# MCU.net
KiCad netlist of a schematic drawn in Altium Designer
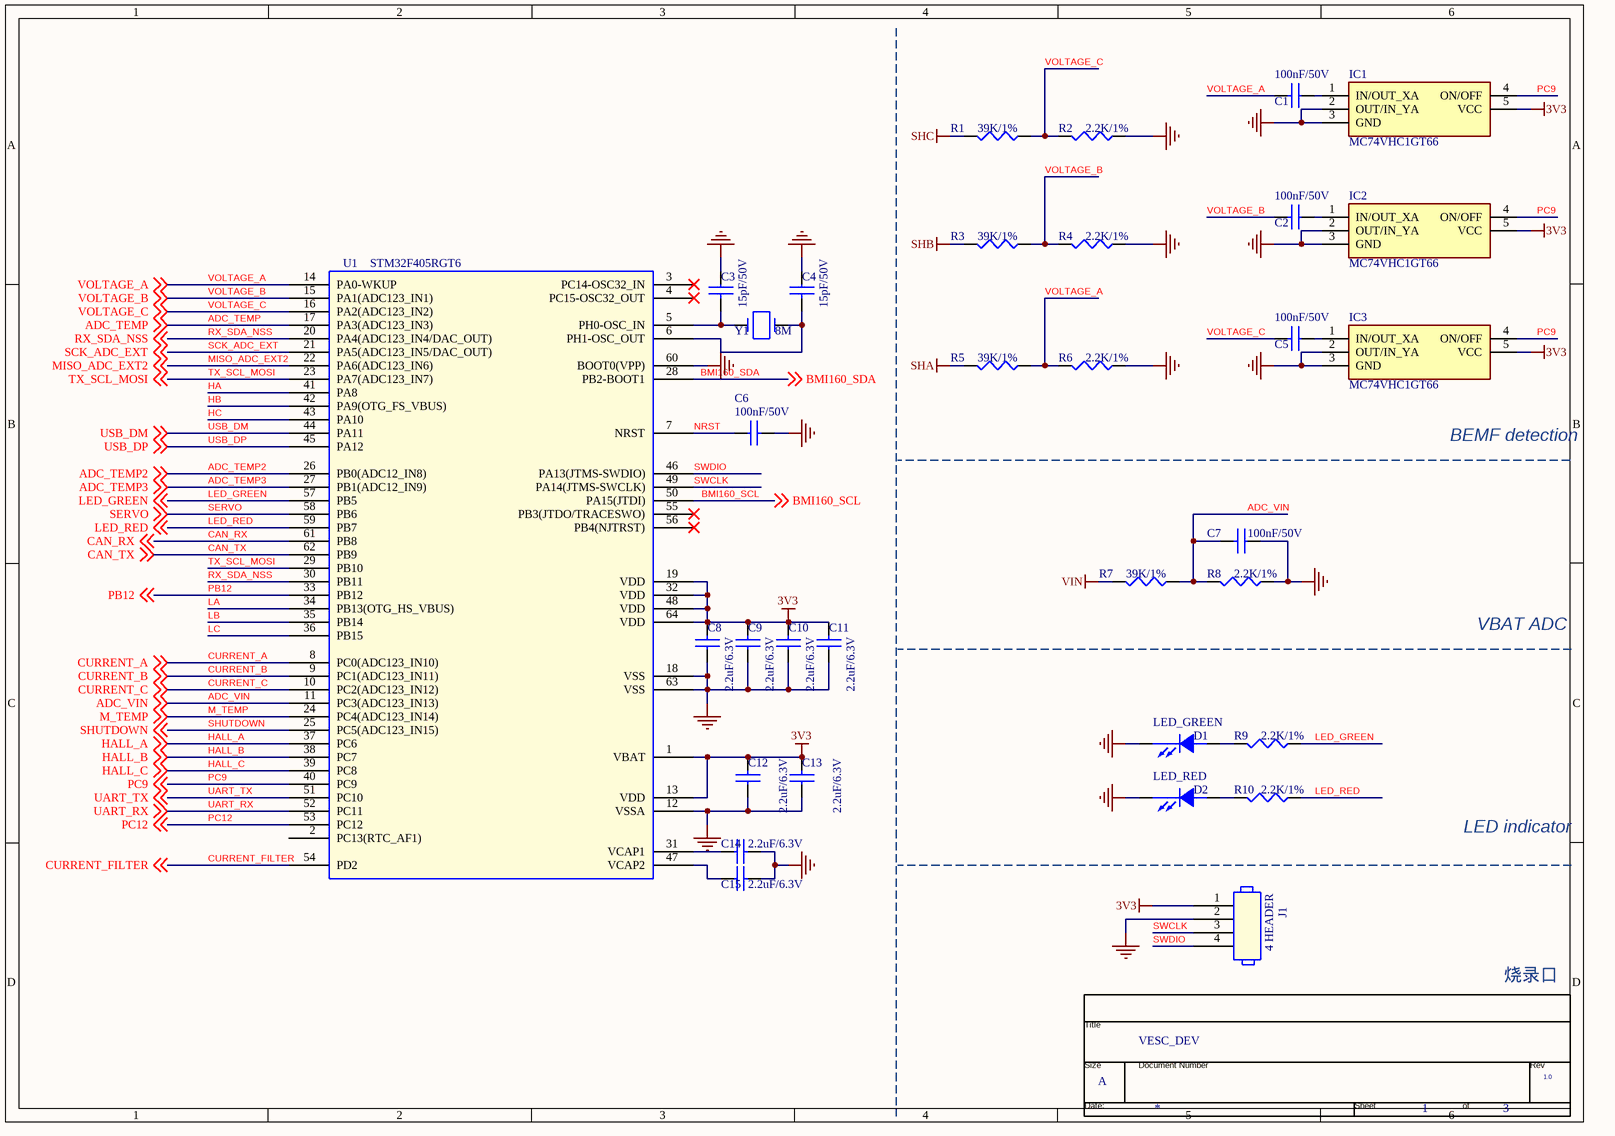
[diagram p0: MCU.SchDoc]

(export (version "E")
  (design (tool "Eeschema 10.0.6"))
  (components
    (comp (ref "C1") (value "100nF/50V") (footprint "C0402") (libsource (lib "*") (part "CAP NP")))
    (comp (ref "C2") (value "100nF/50V") (footprint "C0402") (libsource (lib "*") (part "CAP NP")))
    (comp (ref "C3") (value "15pF/50V") (footprint "C0402") (libsource (lib "*") (part "CAP NP")))
    (comp (ref "C4") (value "15pF/50V") (footprint "C0402") (libsource (lib "*") (part "CAP NP")))
    (comp (ref "C5") (value "100nF/50V") (footprint "C0402") (libsource (lib "*") (part "CAP NP")))
    (comp (ref "C6") (value "100nF/50V") (footprint "C0402") (libsource (lib "*") (part "CAP NP")))
    (comp (ref "C7") (value "100nF/50V") (footprint "C0402") (libsource (lib "*") (part "CAP NP")))
    (comp (ref "C8") (value "2.2uF/6.3V") (footprint "C0402") (libsource (lib "*") (part "CAP NP")))
    (comp (ref "C9") (value "2.2uF/6.3V") (footprint "C0402") (libsource (lib "*") (part "CAP NP")))
    (comp (ref "C10") (value "2.2uF/6.3V") (footprint "C0402") (libsource (lib "*") (part "CAP NP")))
    (comp (ref "C11") (value "2.2uF/6.3V") (footprint "C0402") (libsource (lib "*") (part "CAP NP")))
    (comp (ref "C12") (value "2.2uF/6.3V") (footprint "C0402") (libsource (lib "*") (part "CAP NP")))
    (comp (ref "C13") (value "2.2uF/6.3V") (footprint "C0402") (libsource (lib "*") (part "CAP NP")))
    (comp (ref "C14") (value "2.2uF/6.3V") (footprint "C0402") (libsource (lib "*") (part "CAP NP")))
    (comp (ref "C15") (value "2.2uF/6.3V") (footprint "C0402") (libsource (lib "*") (part "CAP NP")))
    (comp (ref "D1") (value "LED_GREEN") (footprint "LED0603") (libsource (lib "*") (part "LED")))
    (comp (ref "D2") (value "LED_RED") (footprint "LED0603") (libsource (lib "*") (part "LED")))
    (comp (ref "IC1")
      (value "MC74VHC1GT66")
      (footprint "SamacSys:SOT95P275X110-5N")
      (description "Integrated Circuit")
      (libsource (lib "VESC_DEVICE_Library") (part "MC74VHC1GT66"))
    )
    (comp (ref "IC2")
      (value "MC74VHC1GT66")
      (footprint "SamacSys:SOT95P275X110-5N")
      (description "Integrated Circuit")
      (libsource (lib "VESC_DEVICE_Library") (part "MC74VHC1GT66"))
    )
    (comp (ref "IC3")
      (value "MC74VHC1GT66")
      (footprint "SamacSys:SOT95P275X110-5N")
      (description "Integrated Circuit")
      (libsource (lib "VESC_DEVICE_Library") (part "MC74VHC1GT66"))
    )
    (comp (ref "J1") (value "4 HEADER") (footprint "ISP-4P-2_54") (libsource (lib "*") (part "4 HEADER")))
    (comp (ref "R1") (value "39K/1%") (footprint "R0402") (libsource (lib "*") (part "RESISTOR")))
    (comp (ref "R2") (value "2.2K/1%") (footprint "R0402") (libsource (lib "*") (part "RESISTOR")))
    (comp (ref "R3") (value "39K/1%") (footprint "R0402") (libsource (lib "*") (part "RESISTOR")))
    (comp (ref "R4") (value "2.2K/1%") (footprint "R0402") (libsource (lib "*") (part "RESISTOR")))
    (comp (ref "R5") (value "39K/1%") (footprint "R0402") (libsource (lib "*") (part "RESISTOR")))
    (comp (ref "R6") (value "2.2K/1%") (footprint "R0402") (libsource (lib "*") (part "RESISTOR")))
    (comp (ref "R7") (value "39K/1%") (footprint "R0402") (libsource (lib "*") (part "RESISTOR")))
    (comp (ref "R8") (value "2.2K/1%") (footprint "R0402") (libsource (lib "*") (part "RESISTOR")))
    (comp (ref "R9") (value "2.2K/1%") (footprint "R0402") (libsource (lib "*") (part "RESISTOR")))
    (comp (ref "R10") (value "2.2K/1%") (footprint "R0402") (libsource (lib "*") (part "RESISTOR")))
    (comp (ref "U1")
      (value "STM32F405RGT6")
      (footprint "LQFP64_10X10_05P")
      (libsource (lib "*") (part "STM32F405RGT6"))
    )
    (comp (ref "Y1") (value "8M") (footprint "SMD5032-2P") (libsource (lib "*") (part "CRYSTAL")))
  )
  (nets
    (net (code "1") (name "/HA") (class "Default")
      (node (ref "U1") (pin "41") (pinfunction "PA8_41") (pintype "passive"))
    )
    (net (code "2") (name "/HB") (class "Default")
      (node (ref "U1") (pin "42") (pinfunction "PA9(OTG_FS_VBUS)_42") (pintype "passive"))
    )
    (net (code "3") (name "/HC") (class "Default")
      (node (ref "U1") (pin "43") (pinfunction "PA10_43") (pintype "passive"))
    )
    (net (code "4") (name "/LA") (class "Default")
      (node (ref "U1") (pin "34") (pinfunction "PB13(OTG_HS_VBUS)_34") (pintype "passive"))
    )
    (net (code "5") (name "/LB") (class "Default")
      (node (ref "U1") (pin "35") (pinfunction "PB14_35") (pintype "passive"))
    )
    (net (code "6") (name "/LC") (class "Default")
      (node (ref "U1") (pin "36") (pinfunction "PB15_36") (pintype "passive"))
    )
    (net (code "7") (name "/NRST") (class "Default")
      (node (ref "C6") (pin "1") (pinfunction "1_1") (pintype "passive"))
      (node (ref "U1") (pin "7") (pinfunction "NRST_7") (pintype "passive"))
    )
    (net (code "8") (name "/SWCLK") (class "Default")
      (node (ref "J1") (pin "3") (pinfunction "3_3") (pintype "passive"))
      (node (ref "U1") (pin "49") (pinfunction "PA14(JTMS-SWCLK)_49") (pintype "passive"))
    )
    (net (code "9") (name "/SWDIO") (class "Default")
      (node (ref "J1") (pin "4") (pinfunction "4_4") (pintype "passive"))
      (node (ref "U1") (pin "46") (pinfunction "PA13(JTMS-SWDIO)_46") (pintype "passive"))
    )
    (net (code "10") (name "3V3") (class "Default")
      (node (ref "C10") (pin "2") (pinfunction "2_2") (pintype "passive"))
      (node (ref "C11") (pin "2") (pinfunction "2_2") (pintype "passive"))
      (node (ref "C12") (pin "2") (pinfunction "2_2") (pintype "passive"))
      (node (ref "C13") (pin "2") (pinfunction "2_2") (pintype "passive"))
      (node (ref "C8") (pin "2") (pinfunction "2_2") (pintype "passive"))
      (node (ref "C9") (pin "2") (pinfunction "2_2") (pintype "passive"))
      (node (ref "IC1") (pin "5") (pinfunction "VCC_5") (pintype "passive"))
      (node (ref "IC2") (pin "5") (pinfunction "VCC_5") (pintype "passive"))
      (node (ref "IC3") (pin "5") (pinfunction "VCC_5") (pintype "passive"))
      (node (ref "J1") (pin "1") (pinfunction "1_1") (pintype "passive"))
      (node (ref "U1") (pin "1") (pinfunction "VBAT_1") (pintype "power_in"))
      (node (ref "U1") (pin "13") (pinfunction "VDD_13") (pintype "power_in"))
      (node (ref "U1") (pin "19") (pinfunction "VDD_19") (pintype "power_in"))
      (node (ref "U1") (pin "32") (pinfunction "VDD_32") (pintype "power_in"))
      (node (ref "U1") (pin "48") (pinfunction "VDD_48") (pintype "power_in"))
      (node (ref "U1") (pin "64") (pinfunction "VDD_64") (pintype "power_in"))
    )
    (net (code "11") (name "ADC_TEMP") (class "Default")
      (node (ref "U1") (pin "17") (pinfunction "PA3(ADC123_IN3)_17") (pintype "passive"))
    )
    (net (code "12") (name "ADC_TEMP2") (class "Default")
      (node (ref "U1") (pin "26") (pinfunction "PB0(ADC12_IN8)_26") (pintype "passive"))
    )
    (net (code "13") (name "ADC_TEMP3") (class "Default")
      (node (ref "U1") (pin "27") (pinfunction "PB1(ADC12_IN9)_27") (pintype "passive"))
    )
    (net (code "14") (name "ADC_VIN") (class "Default")
      (node (ref "C7") (pin "2") (pinfunction "2_2") (pintype "passive"))
      (node (ref "R7") (pin "1") (pinfunction "1_1") (pintype "passive"))
      (node (ref "R8") (pin "2") (pinfunction "2_2") (pintype "passive"))
      (node (ref "U1") (pin "11") (pinfunction "PC3(ADC123_IN13)_11") (pintype "passive"))
    )
    (net (code "15") (name "BMI160_SCL") (class "Default")
      (node (ref "U1") (pin "50") (pinfunction "PA15(JTDI)_50") (pintype "passive"))
    )
    (net (code "16") (name "BMI160_SDA") (class "Default")
      (node (ref "U1") (pin "28") (pinfunction "PB2-BOOT1_28") (pintype "passive"))
    )
    (net (code "17") (name "CAN_RX") (class "Default")
      (node (ref "U1") (pin "61") (pinfunction "PB8_61") (pintype "passive"))
    )
    (net (code "18") (name "CAN_TX") (class "Default")
      (node (ref "U1") (pin "62") (pinfunction "PB9_62") (pintype "passive"))
    )
    (net (code "19") (name "CURRENT_A") (class "Default")
      (node (ref "U1") (pin "8") (pinfunction "PC0(ADC123_IN10)_8") (pintype "passive"))
    )
    (net (code "20") (name "CURRENT_B") (class "Default")
      (node (ref "U1") (pin "9") (pinfunction "PC1(ADC123_IN11)_9") (pintype "passive"))
    )
    (net (code "21") (name "CURRENT_C") (class "Default")
      (node (ref "U1") (pin "10") (pinfunction "PC2(ADC123_IN12)_10") (pintype "passive"))
    )
    (net (code "22") (name "CURRENT_FILTER") (class "Default")
      (node (ref "U1") (pin "54") (pinfunction "PD2_54") (pintype "passive"))
    )
    (net (code "23") (name "GND") (class "Default")
      (node (ref "C10") (pin "1") (pinfunction "1_1") (pintype "passive"))
      (node (ref "C11") (pin "1") (pinfunction "1_1") (pintype "passive"))
      (node (ref "C12") (pin "1") (pinfunction "1_1") (pintype "passive"))
      (node (ref "C13") (pin "1") (pinfunction "1_1") (pintype "passive"))
      (node (ref "C14") (pin "2") (pinfunction "2_2") (pintype "passive"))
      (node (ref "C15") (pin "2") (pinfunction "2_2") (pintype "passive"))
      (node (ref "C3") (pin "1") (pinfunction "1_1") (pintype "passive"))
      (node (ref "C4") (pin "1") (pinfunction "1_1") (pintype "passive"))
      (node (ref "C6") (pin "2") (pinfunction "2_2") (pintype "passive"))
      (node (ref "C7") (pin "1") (pinfunction "1_1") (pintype "passive"))
      (node (ref "C8") (pin "1") (pinfunction "1_1") (pintype "passive"))
      (node (ref "C9") (pin "1") (pinfunction "1_1") (pintype "passive"))
      (node (ref "D1") (pin "1") (pinfunction "CATHODE_1") (pintype "passive"))
      (node (ref "D2") (pin "1") (pinfunction "CATHODE_1") (pintype "passive"))
      (node (ref "IC1") (pin "2") (pinfunction "OUT/IN_YA_2") (pintype "passive"))
      (node (ref "IC1") (pin "3") (pinfunction "GND_3") (pintype "passive"))
      (node (ref "IC2") (pin "2") (pinfunction "OUT/IN_YA_2") (pintype "passive"))
      (node (ref "IC2") (pin "3") (pinfunction "GND_3") (pintype "passive"))
      (node (ref "IC3") (pin "2") (pinfunction "OUT/IN_YA_2") (pintype "passive"))
      (node (ref "IC3") (pin "3") (pinfunction "GND_3") (pintype "passive"))
      (node (ref "J1") (pin "2") (pinfunction "2_2") (pintype "passive"))
      (node (ref "R2") (pin "1") (pinfunction "1_1") (pintype "passive"))
      (node (ref "R4") (pin "1") (pinfunction "1_1") (pintype "passive"))
      (node (ref "R6") (pin "1") (pinfunction "1_1") (pintype "passive"))
      (node (ref "R8") (pin "1") (pinfunction "1_1") (pintype "passive"))
      (node (ref "U1") (pin "12") (pinfunction "VSSA_12") (pintype "power_in"))
      (node (ref "U1") (pin "18") (pinfunction "VSS_18") (pintype "power_in"))
      (node (ref "U1") (pin "60") (pinfunction "BOOT0(VPP)_60") (pintype "passive"))
      (node (ref "U1") (pin "63") (pinfunction "VSS_63") (pintype "power_in"))
    )
    (net (code "24") (name "HALL_A") (class "Default")
      (node (ref "U1") (pin "37") (pinfunction "PC6_37") (pintype "passive"))
    )
    (net (code "25") (name "HALL_B") (class "Default")
      (node (ref "U1") (pin "38") (pinfunction "PC7_38") (pintype "passive"))
    )
    (net (code "26") (name "HALL_C") (class "Default")
      (node (ref "U1") (pin "39") (pinfunction "PC8_39") (pintype "passive"))
    )
    (net (code "27") (name "LED_GREEN") (class "Default")
      (node (ref "R9") (pin "1") (pinfunction "1_1") (pintype "passive"))
      (node (ref "U1") (pin "57") (pinfunction "PB5_57") (pintype "passive"))
    )
    (net (code "28") (name "LED_RED") (class "Default")
      (node (ref "R10") (pin "1") (pinfunction "1_1") (pintype "passive"))
      (node (ref "U1") (pin "59") (pinfunction "PB7_59") (pintype "passive"))
    )
    (net (code "29") (name "MISO_ADC_EXT2") (class "Default")
      (node (ref "U1") (pin "22") (pinfunction "PA6(ADC123_IN6)_22") (pintype "passive"))
    )
    (net (code "30") (name "M_TEMP") (class "Default")
      (node (ref "U1") (pin "24") (pinfunction "PC4(ADC123_IN14)_24") (pintype "passive"))
    )
    (net (code "31") (name "Net-(D1-ANODE)") (class "Default")
      (node (ref "D1") (pin "2") (pinfunction "ANODE_2") (pintype "passive"))
      (node (ref "R9") (pin "2") (pinfunction "2_2") (pintype "passive"))
    )
    (net (code "32") (name "Net-(D2-ANODE)") (class "Default")
      (node (ref "D2") (pin "2") (pinfunction "ANODE_2") (pintype "passive"))
      (node (ref "R10") (pin "2") (pinfunction "2_2") (pintype "passive"))
    )
    (net (code "33") (name "Net-(IC1-IN{slash}OUT_XA)") (class "Default")
      (node (ref "C1") (pin "1") (pinfunction "1_1") (pintype "passive"))
      (node (ref "IC1") (pin "1") (pinfunction "IN/OUT_XA_1") (pintype "passive"))
    )
    (net (code "34") (name "Net-(IC2-IN{slash}OUT_XA)") (class "Default")
      (node (ref "C2") (pin "1") (pinfunction "1_1") (pintype "passive"))
      (node (ref "IC2") (pin "1") (pinfunction "IN/OUT_XA_1") (pintype "passive"))
    )
    (net (code "35") (name "Net-(IC3-IN{slash}OUT_XA)") (class "Default")
      (node (ref "C5") (pin "1") (pinfunction "1_1") (pintype "passive"))
      (node (ref "IC3") (pin "1") (pinfunction "IN/OUT_XA_1") (pintype "passive"))
    )
    (net (code "36") (name "Net-(U1-PH0-OSC_IN)") (class "Default")
      (node (ref "C3") (pin "2") (pinfunction "2_2") (pintype "passive"))
      (node (ref "U1") (pin "5") (pinfunction "PH0-OSC_IN_5") (pintype "passive"))
      (node (ref "Y1") (pin "2") (pinfunction "2_2") (pintype "passive"))
    )
    (net (code "37") (name "Net-(U1-PH1-OSC_OUT)") (class "Default")
      (node (ref "C4") (pin "2") (pinfunction "2_2") (pintype "passive"))
      (node (ref "U1") (pin "6") (pinfunction "PH1-OSC_OUT_6") (pintype "passive"))
      (node (ref "Y1") (pin "1") (pinfunction "1_1") (pintype "passive"))
    )
    (net (code "38") (name "Net-(U1-VCAP1)") (class "Default")
      (node (ref "C14") (pin "1") (pinfunction "1_1") (pintype "passive"))
      (node (ref "U1") (pin "31") (pinfunction "VCAP1_31") (pintype "passive"))
    )
    (net (code "39") (name "Net-(U1-VCAP2)") (class "Default")
      (node (ref "C15") (pin "1") (pinfunction "1_1") (pintype "passive"))
      (node (ref "U1") (pin "47") (pinfunction "VCAP2_47") (pintype "passive"))
    )
    (net (code "40") (name "PB12") (class "Default")
      (node (ref "U1") (pin "33") (pinfunction "PB12_33") (pintype "passive"))
    )
    (net (code "41") (name "PC9") (class "Default")
      (node (ref "IC1") (pin "4") (pinfunction "ON/OFF_4") (pintype "passive"))
      (node (ref "IC2") (pin "4") (pinfunction "ON/OFF_4") (pintype "passive"))
      (node (ref "IC3") (pin "4") (pinfunction "ON/OFF_4") (pintype "passive"))
      (node (ref "U1") (pin "40") (pinfunction "PC9_40") (pintype "passive"))
    )
    (net (code "42") (name "PC12") (class "Default")
      (node (ref "U1") (pin "53") (pinfunction "PC12_53") (pintype "passive"))
    )
    (net (code "43") (name "RX_SDA_NSS") (class "Default")
      (node (ref "U1") (pin "20") (pinfunction "PA4(ADC123_IN4/DAC_OUT)_20") (pintype "passive"))
      (node (ref "U1") (pin "30") (pinfunction "PB11_30") (pintype "passive"))
    )
    (net (code "44") (name "SCK_ADC_EXT") (class "Default")
      (node (ref "U1") (pin "21") (pinfunction "PA5(ADC123_IN5/DAC_OUT)_21") (pintype "passive"))
    )
    (net (code "45") (name "SERVO") (class "Default")
      (node (ref "U1") (pin "58") (pinfunction "PB6_58") (pintype "passive"))
    )
    (net (code "46") (name "SHA") (class "Default")
      (node (ref "R5") (pin "2") (pinfunction "2_2") (pintype "passive"))
    )
    (net (code "47") (name "SHB") (class "Default")
      (node (ref "R3") (pin "2") (pinfunction "2_2") (pintype "passive"))
    )
    (net (code "48") (name "SHC") (class "Default")
      (node (ref "R1") (pin "2") (pinfunction "2_2") (pintype "passive"))
    )
    (net (code "49") (name "SHUTDOWN") (class "Default")
      (node (ref "U1") (pin "25") (pinfunction "PC5(ADC123_IN15)_25") (pintype "passive"))
    )
    (net (code "50") (name "TX_SCL_MOSI") (class "Default")
      (node (ref "U1") (pin "23") (pinfunction "PA7(ADC123_IN7)_23") (pintype "passive"))
      (node (ref "U1") (pin "29") (pinfunction "PB10_29") (pintype "passive"))
    )
    (net (code "51") (name "UART_RX") (class "Default")
      (node (ref "U1") (pin "52") (pinfunction "PC11_52") (pintype "passive"))
    )
    (net (code "52") (name "UART_TX") (class "Default")
      (node (ref "U1") (pin "51") (pinfunction "PC10_51") (pintype "passive"))
    )
    (net (code "53") (name "USB_DM") (class "Default")
      (node (ref "U1") (pin "44") (pinfunction "PA11_44") (pintype "passive"))
    )
    (net (code "54") (name "USB_DP") (class "Default")
      (node (ref "U1") (pin "45") (pinfunction "PA12_45") (pintype "passive"))
    )
    (net (code "55") (name "VIN") (class "Default")
      (node (ref "R7") (pin "2") (pinfunction "2_2") (pintype "passive"))
    )
    (net (code "56") (name "VOLTAGE_A") (class "Default")
      (node (ref "C1") (pin "2") (pinfunction "2_2") (pintype "passive"))
      (node (ref "R5") (pin "1") (pinfunction "1_1") (pintype "passive"))
      (node (ref "R6") (pin "2") (pinfunction "2_2") (pintype "passive"))
      (node (ref "U1") (pin "14") (pinfunction "PA0-WKUP_14") (pintype "passive"))
    )
    (net (code "57") (name "VOLTAGE_B") (class "Default")
      (node (ref "C2") (pin "2") (pinfunction "2_2") (pintype "passive"))
      (node (ref "R3") (pin "1") (pinfunction "1_1") (pintype "passive"))
      (node (ref "R4") (pin "2") (pinfunction "2_2") (pintype "passive"))
      (node (ref "U1") (pin "15") (pinfunction "PA1(ADC123_IN1)_15") (pintype "passive"))
    )
    (net (code "58") (name "VOLTAGE_C") (class "Default")
      (node (ref "C5") (pin "2") (pinfunction "2_2") (pintype "passive"))
      (node (ref "R1") (pin "1") (pinfunction "1_1") (pintype "passive"))
      (node (ref "R2") (pin "2") (pinfunction "2_2") (pintype "passive"))
      (node (ref "U1") (pin "16") (pinfunction "PA2(ADC123_IN2)_16") (pintype "passive"))
    )
    (net (code "59") (name "unconnected-(U1-PB3(JTDO{slash}TRACESWO)-Pad55)") (class "Default")
      (node (ref "U1") (pin "55") (pinfunction "PB3(JTDO/TRACESWO)_55") (pintype "passive+no_connect"))
    )
    (net (code "60") (name "unconnected-(U1-PB4(NJTRST)-Pad56)") (class "Default")
      (node (ref "U1") (pin "56") (pinfunction "PB4(NJTRST)_56") (pintype "passive+no_connect"))
    )
    (net (code "61") (name "unconnected-(U1-PC13(RTC_AF1)-Pad2)") (class "Default")
      (node (ref "U1") (pin "2") (pinfunction "PC13(RTC_AF1)_2") (pintype "passive"))
    )
    (net (code "62") (name "unconnected-(U1-PC14-OSC32_IN-Pad3)") (class "Default")
      (node (ref "U1") (pin "3") (pinfunction "PC14-OSC32_IN_3") (pintype "passive+no_connect"))
    )
    (net (code "63") (name "unconnected-(U1-PC15-OSC32_OUT-Pad4)") (class "Default")
      (node (ref "U1") (pin "4") (pinfunction "PC15-OSC32_OUT_4") (pintype "passive+no_connect"))
    )
  )
)
